# LMP91000.net
KiCad netlist of a schematic drawn in EAGLE
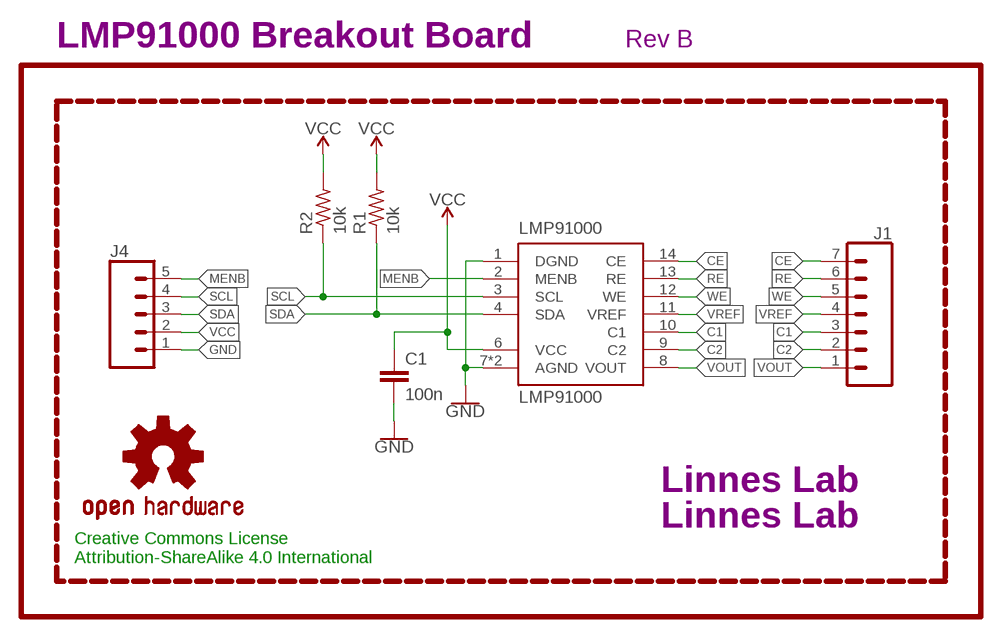
[diagram p0: schematic, sheet 1]

(export (version "E")
  (design (tool "Eeschema 10.0.6"))
  (components
    (comp (ref "C1")
      (value "100n")
      (footprint "eagle-import:C0402")
      (libsource (lib "eagle-import") (part "CAPACITOR0402"))
    )
    (comp (ref "J1")
      (value "CONN_07NO_SILK")
      (footprint "eagle-import:1X07_NO_SILK")
      (libsource (lib "eagle-import") (part "CONN_07NO_SILK"))
    )
    (comp (ref "J4")
      (value "CONN_05NO_SILK")
      (footprint "eagle-import:1X05_NO_SILK")
      (libsource (lib "eagle-import") (part "CONN_05NO_SILK"))
    )
    (comp (ref "LMP91000")
      (value "LMP91000")
      (footprint "eagle-import:WSON-14")
      (libsource (lib "eagle-import") (part "LMP91000"))
    )
    (comp (ref "LOGO1")
      (value "OSHW-LOGOS")
      (footprint "eagle-import:OSHW-LOGO-S")
      (libsource (lib "eagle-import") (part "OSHW-LOGOS"))
    )
    (comp (ref "R1")
      (value "10k")
      (footprint "eagle-import:R0402")
      (libsource (lib "eagle-import") (part "RESISTOR0402"))
    )
    (comp (ref "R2")
      (value "10k")
      (footprint "eagle-import:R0402")
      (libsource (lib "eagle-import") (part "RESISTOR0402"))
    )
    (comp (ref "U$1")
      (value "LINNES.LAB.05")
      (footprint "eagle-import:LINNES.LAB.05")
      (libsource (lib "eagle-import") (part "LINNES.LAB.05"))
    )
    (comp (ref "U$2")
      (value "LINNES.LAB.LOGO")
      (footprint "eagle-import:LINNES.LAB.LOGO")
      (libsource (lib "eagle-import") (part "LINNES.LAB.LOGO"))
    )
    (comp (ref "U$3")
      (value "REVISION.B")
      (footprint "eagle-import:REV.B")
      (libsource (lib "eagle-import") (part "REVISION.B"))
    )
  )
  (nets
    (net (code "1") (name "C1") (class "Default")
      (node (ref "J1") (pin "3") (pinfunction "3_3") (pintype "passive"))
      (node (ref "LMP91000") (pin "10") (pinfunction "C1_10") (pintype "bidirectional"))
    )
    (net (code "2") (name "C2") (class "Default")
      (node (ref "J1") (pin "2") (pinfunction "2_2") (pintype "passive"))
      (node (ref "LMP91000") (pin "9") (pinfunction "C2_9") (pintype "bidirectional"))
    )
    (net (code "3") (name "CE") (class "Default")
      (node (ref "J1") (pin "7") (pinfunction "7_7") (pintype "passive"))
      (node (ref "LMP91000") (pin "14") (pinfunction "CE_14") (pintype "bidirectional"))
    )
    (net (code "4") (name "GND") (class "Default")
      (node (ref "C1") (pin "2") (pinfunction "2_2") (pintype "passive"))
      (node (ref "J4") (pin "1") (pinfunction "1_1") (pintype "passive"))
      (node (ref "LMP91000") (pin "1") (pinfunction "DGND_1") (pintype "bidirectional"))
      (node (ref "LMP91000") (pin "7") (pinfunction "AGND_7") (pintype "bidirectional"))
      (node (ref "LMP91000") (pin "DAP") (pinfunction "AGND_DAP") (pintype "bidirectional"))
    )
    (net (code "5") (name "MENB") (class "Default")
      (node (ref "J4") (pin "5") (pinfunction "5_5") (pintype "passive"))
      (node (ref "LMP91000") (pin "2") (pinfunction "MENB_2") (pintype "bidirectional"))
    )
    (net (code "6") (name "RE") (class "Default")
      (node (ref "J1") (pin "6") (pinfunction "6_6") (pintype "passive"))
      (node (ref "LMP91000") (pin "13") (pinfunction "RE_13") (pintype "bidirectional"))
    )
    (net (code "7") (name "SCL") (class "Default")
      (node (ref "J4") (pin "4") (pinfunction "4_4") (pintype "passive"))
      (node (ref "LMP91000") (pin "3") (pinfunction "SCL_3") (pintype "bidirectional"))
      (node (ref "R2") (pin "1") (pinfunction "1_1") (pintype "passive"))
    )
    (net (code "8") (name "SDA") (class "Default")
      (node (ref "J4") (pin "3") (pinfunction "3_3") (pintype "passive"))
      (node (ref "LMP91000") (pin "4") (pinfunction "SDA_4") (pintype "bidirectional"))
      (node (ref "R1") (pin "1") (pinfunction "1_1") (pintype "passive"))
    )
    (net (code "9") (name "VCC") (class "Default")
      (node (ref "C1") (pin "1") (pinfunction "1_1") (pintype "passive"))
      (node (ref "J4") (pin "2") (pinfunction "2_2") (pintype "passive"))
      (node (ref "LMP91000") (pin "6") (pinfunction "VCC_6") (pintype "bidirectional"))
      (node (ref "R1") (pin "2") (pinfunction "2_2") (pintype "passive"))
      (node (ref "R2") (pin "2") (pinfunction "2_2") (pintype "passive"))
    )
    (net (code "10") (name "VOUT") (class "Default")
      (node (ref "J1") (pin "1") (pinfunction "1_1") (pintype "passive"))
      (node (ref "LMP91000") (pin "8") (pinfunction "VOUT_8") (pintype "bidirectional"))
    )
    (net (code "11") (name "VREF") (class "Default")
      (node (ref "J1") (pin "4") (pinfunction "4_4") (pintype "passive"))
      (node (ref "LMP91000") (pin "11") (pinfunction "VREF_11") (pintype "bidirectional"))
    )
    (net (code "12") (name "WE") (class "Default")
      (node (ref "J1") (pin "5") (pinfunction "5_5") (pintype "passive"))
      (node (ref "LMP91000") (pin "12") (pinfunction "WE_12") (pintype "bidirectional"))
    )
  )
)
